# megausb.net
KiCad netlist of a schematic drawn in EAGLE
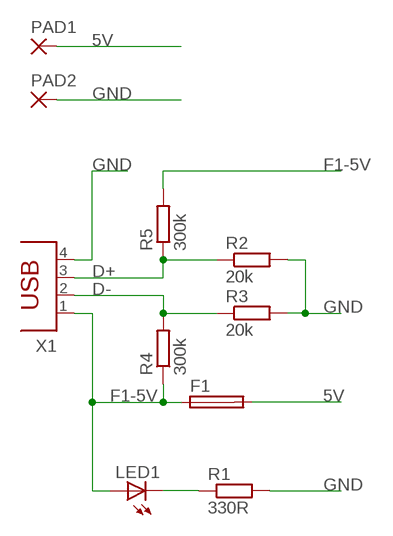
[diagram p0: schematic, sheet 1]

(export (version "E")
  (design (tool "Eeschema 10.0.6"))
  (components
    (comp (ref "F1")
      (value "TE5")
      (footprint "eagle-import:TE5")
      (libsource (lib "eagle-import") (part "TE5"))
    )
    (comp (ref "LED1")
      (value "LED5MM")
      (footprint "eagle-import:LED5MM")
      (libsource (lib "eagle-import") (part "LED5MM"))
    )
    (comp (ref "PAD1")
      (value "3,81/1,1")
      (footprint "eagle-import:3,81_1,1")
      (libsource (lib "eagle-import") (part "3,81/1,1"))
    )
    (comp (ref "PAD2")
      (value "3,81/1,1")
      (footprint "eagle-import:3,81_1,1")
      (libsource (lib "eagle-import") (part "3,81/1,1"))
    )
    (comp (ref "R1")
      (value "330R")
      (footprint "eagle-import:0204_5")
      (libsource (lib "eagle-import") (part "R-EU_0204/5"))
    )
    (comp (ref "R2")
      (value "20k")
      (footprint "eagle-import:0204_5")
      (libsource (lib "eagle-import") (part "R-EU_0204/5"))
    )
    (comp (ref "R3")
      (value "20k")
      (footprint "eagle-import:0204_5")
      (libsource (lib "eagle-import") (part "R-EU_0204/5"))
    )
    (comp (ref "R4")
      (value "300k")
      (footprint "eagle-import:0204_5")
      (libsource (lib "eagle-import") (part "R-EU_0204/5"))
    )
    (comp (ref "R5")
      (value "300k")
      (footprint "eagle-import:0204_5")
      (libsource (lib "eagle-import") (part "R-EU_0204/5"))
    )
    (comp (ref "X1")
      (value "PN87520")
      (footprint "eagle-import:PN87520")
      (libsource (lib "eagle-import") (part "PN87520"))
    )
  )
  (nets
    (net (code "1") (name "/5V") (class "Default")
      (node (ref "F1") (pin "2") (pinfunction "2_2") (pintype "passive"))
      (node (ref "PAD1") (pin "1") (pinfunction "P_1") (pintype "passive"))
    )
    (net (code "2") (name "/D+") (class "Default")
      (node (ref "R2") (pin "1") (pinfunction "1_1") (pintype "passive"))
      (node (ref "R5") (pin "1") (pinfunction "1_1") (pintype "passive"))
      (node (ref "X1") (pin "3") (pinfunction "3_3") (pintype "passive"))
    )
    (net (code "3") (name "/D-") (class "Default")
      (node (ref "R3") (pin "1") (pinfunction "1_1") (pintype "passive"))
      (node (ref "R4") (pin "2") (pinfunction "2_2") (pintype "passive"))
      (node (ref "X1") (pin "2") (pinfunction "2_2") (pintype "passive"))
    )
    (net (code "4") (name "/F1-5V") (class "Default")
      (node (ref "F1") (pin "1") (pinfunction "1_1") (pintype "passive"))
      (node (ref "LED1") (pin "A") (pinfunction "A_A") (pintype "passive"))
      (node (ref "R4") (pin "1") (pinfunction "1_1") (pintype "passive"))
      (node (ref "R5") (pin "2") (pinfunction "2_2") (pintype "passive"))
      (node (ref "X1") (pin "1") (pinfunction "1_1") (pintype "passive"))
    )
    (net (code "5") (name "/GND") (class "Default")
      (node (ref "PAD2") (pin "1") (pinfunction "P_1") (pintype "passive"))
      (node (ref "R1") (pin "2") (pinfunction "2_2") (pintype "passive"))
      (node (ref "R2") (pin "2") (pinfunction "2_2") (pintype "passive"))
      (node (ref "R3") (pin "2") (pinfunction "2_2") (pintype "passive"))
      (node (ref "X1") (pin "4") (pinfunction "4_4") (pintype "passive"))
    )
    (net (code "6") (name "Net-(LED1-C)") (class "Default")
      (node (ref "LED1") (pin "K") (pinfunction "C_K") (pintype "passive"))
      (node (ref "R1") (pin "1") (pinfunction "1_1") (pintype "passive"))
    )
  )
)
